# IOT_Sheet.net
KiCad netlist of a schematic drawn in Altium Designer
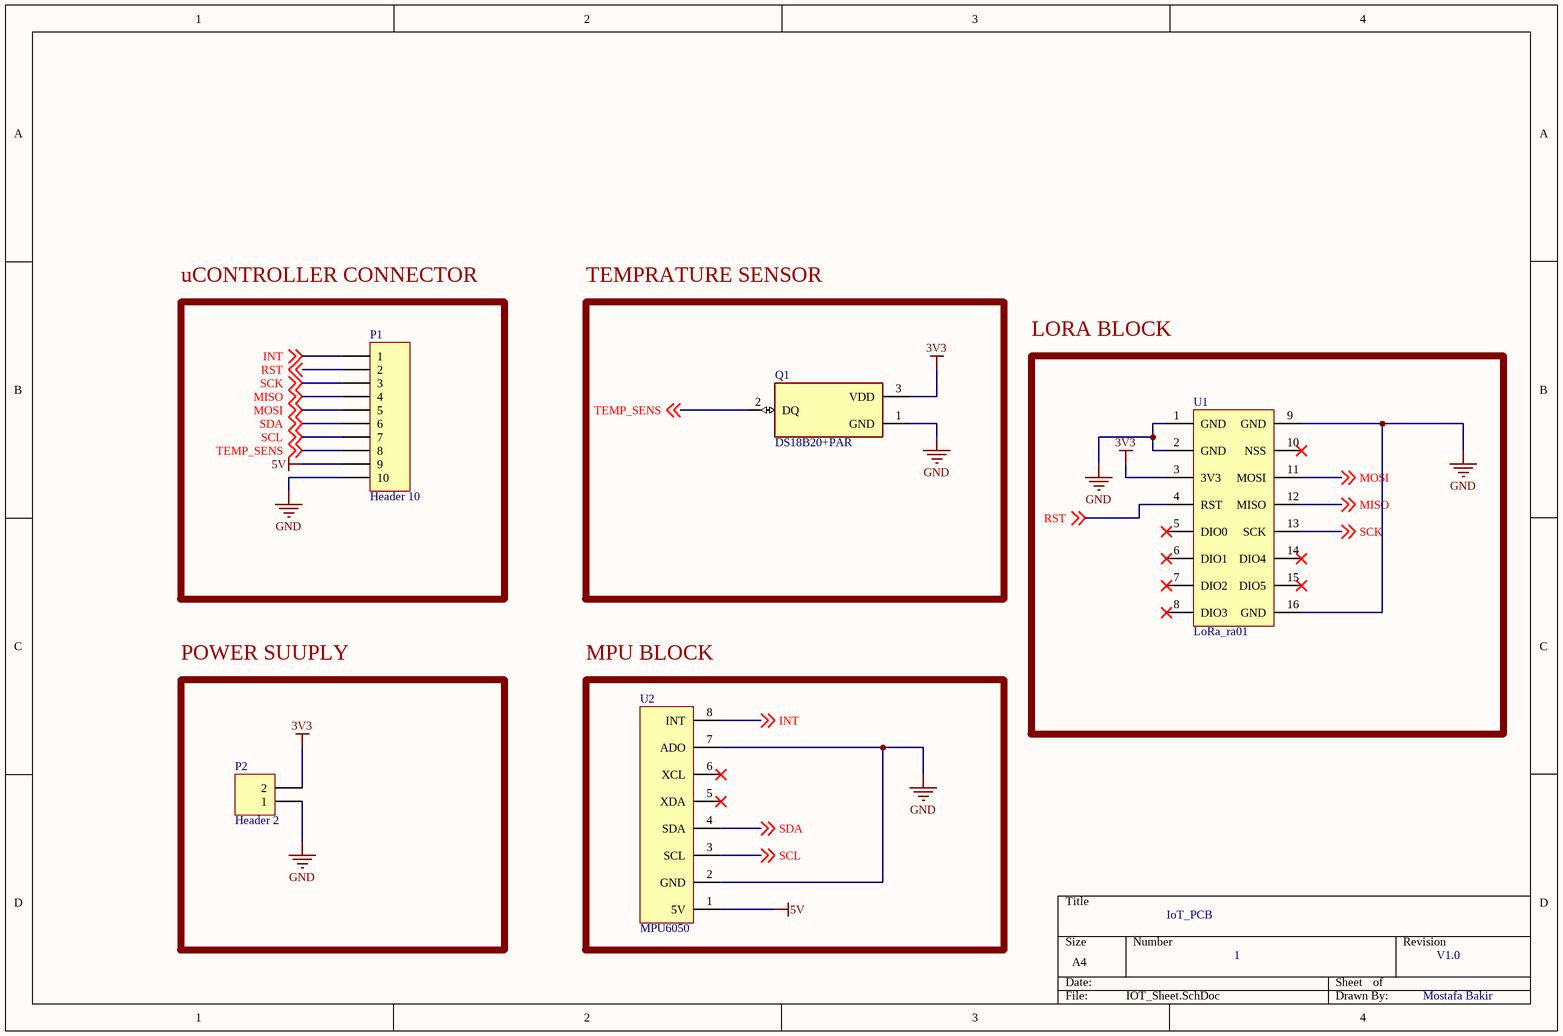
[diagram p0: IOT_Sheet.SchDoc]

(export (version "E")
  (design (tool "Eeschema 10.0.6"))
  (components
    (comp (ref "P1")
      (value "Header 10")
      (footprint "HDR1X10")
      (description "Header, 10-Pin")
      (fields (field (name "PUBLISHER") "Altium Limited"))
      (libsource (lib "Miscellaneous Connectors") (part "Header 10"))
    )
    (comp (ref "P2")
      (value "Header 2")
      (footprint "HDR1X2")
      (description "Header, 2-Pin")
      (fields (field (name "PUBLISHER") "Altium Limited"))
      (libsource (lib "Miscellaneous Connectors") (part "Header 2"))
    )
    (comp (ref "Q1")
      (value "DS18B20+PAR")
      (footprint "TO-92")
      (description "Temperature Sensor Digital, Local -55Â°C ~ 125Â°C 12 b TO-92-3")
      (fields (field (name "MF") "Maxim Integrated"))
      (libsource (lib "Schlib1") (part "DS18B20+PAR"))
    )
    (comp (ref "U1")
      (value "LoRa_ra01")
      (footprint "LoRa_pcblib")
      (libsource (lib "Schlib1") (part "Lora module sx1278"))
    )
    (comp (ref "U2") (value "MPU6050") (footprint "MPU6050") (libsource (lib "Schlib1") (part "MPU6050")))
  )
  (nets
    (net (code "1") (name "3V3") (class "Default")
      (node (ref "P2") (pin "2") (pinfunction "2_2") (pintype "passive"))
      (node (ref "Q1") (pin "3") (pinfunction "VDD_3") (pintype "power_in"))
      (node (ref "U1") (pin "3") (pinfunction "3V3_3") (pintype "passive"))
    )
    (net (code "2") (name "5V") (class "Default")
      (node (ref "P1") (pin "9") (pinfunction "9_9") (pintype "passive"))
      (node (ref "U2") (pin "1") (pinfunction "5V_1") (pintype "passive"))
    )
    (net (code "3") (name "GND") (class "Default")
      (node (ref "P1") (pin "10") (pinfunction "10_10") (pintype "passive"))
      (node (ref "P2") (pin "1") (pinfunction "1_1") (pintype "passive"))
      (node (ref "Q1") (pin "1") (pinfunction "GND_1") (pintype "power_in"))
      (node (ref "U1") (pin "1") (pinfunction "GND_1") (pintype "passive"))
      (node (ref "U1") (pin "16") (pinfunction "GND_16") (pintype "passive"))
      (node (ref "U1") (pin "2") (pinfunction "GND_2") (pintype "passive"))
      (node (ref "U1") (pin "9") (pinfunction "GND_9") (pintype "passive"))
      (node (ref "U2") (pin "2") (pinfunction "GND_2") (pintype "passive"))
      (node (ref "U2") (pin "7") (pinfunction "ADO_7") (pintype "passive"))
    )
    (net (code "4") (name "INT") (class "Default")
      (node (ref "P1") (pin "1") (pinfunction "1_1") (pintype "passive"))
      (node (ref "U2") (pin "8") (pinfunction "INT_8") (pintype "passive"))
    )
    (net (code "5") (name "MISO") (class "Default")
      (node (ref "P1") (pin "4") (pinfunction "4_4") (pintype "passive"))
      (node (ref "U1") (pin "12") (pinfunction "MISO_12") (pintype "passive"))
    )
    (net (code "6") (name "MOSI") (class "Default")
      (node (ref "P1") (pin "5") (pinfunction "5_5") (pintype "passive"))
      (node (ref "U1") (pin "11") (pinfunction "MOSI_11") (pintype "passive"))
    )
    (net (code "7") (name "RST") (class "Default")
      (node (ref "P1") (pin "2") (pinfunction "2_2") (pintype "passive"))
      (node (ref "U1") (pin "4") (pinfunction "RST_4") (pintype "passive"))
    )
    (net (code "8") (name "SCK") (class "Default")
      (node (ref "P1") (pin "3") (pinfunction "3_3") (pintype "passive"))
      (node (ref "U1") (pin "13") (pinfunction "SCK_13") (pintype "passive"))
    )
    (net (code "9") (name "SCL") (class "Default")
      (node (ref "P1") (pin "7") (pinfunction "7_7") (pintype "passive"))
      (node (ref "U2") (pin "3") (pinfunction "SCL_3") (pintype "passive"))
    )
    (net (code "10") (name "SDA") (class "Default")
      (node (ref "P1") (pin "6") (pinfunction "6_6") (pintype "passive"))
      (node (ref "U2") (pin "4") (pinfunction "SDA_4") (pintype "passive"))
    )
    (net (code "11") (name "TEMP_SENS") (class "Default")
      (node (ref "P1") (pin "8") (pinfunction "8_8") (pintype "passive"))
      (node (ref "Q1") (pin "2") (pinfunction "DQ_2") (pintype "bidirectional"))
    )
    (net (code "12") (name "unconnected-(U1-DIO0-Pad5)") (class "Default")
      (node (ref "U1") (pin "5") (pinfunction "DIO0_5") (pintype "passive+no_connect"))
    )
    (net (code "13") (name "unconnected-(U1-DIO1-Pad6)") (class "Default")
      (node (ref "U1") (pin "6") (pinfunction "DIO1_6") (pintype "passive+no_connect"))
    )
    (net (code "14") (name "unconnected-(U1-DIO2-Pad7)") (class "Default")
      (node (ref "U1") (pin "7") (pinfunction "DIO2_7") (pintype "passive+no_connect"))
    )
    (net (code "15") (name "unconnected-(U1-DIO3-Pad8)") (class "Default")
      (node (ref "U1") (pin "8") (pinfunction "DIO3_8") (pintype "passive+no_connect"))
    )
    (net (code "16") (name "unconnected-(U1-DIO4-Pad14)") (class "Default")
      (node (ref "U1") (pin "14") (pinfunction "DIO4_14") (pintype "passive+no_connect"))
    )
    (net (code "17") (name "unconnected-(U1-DIO5-Pad15)") (class "Default")
      (node (ref "U1") (pin "15") (pinfunction "DIO5_15") (pintype "passive+no_connect"))
    )
    (net (code "18") (name "unconnected-(U1-NSS-Pad10)") (class "Default")
      (node (ref "U1") (pin "10") (pinfunction "NSS_10") (pintype "passive+no_connect"))
    )
    (net (code "19") (name "unconnected-(U2-XCL-Pad6)") (class "Default")
      (node (ref "U2") (pin "6") (pinfunction "XCL_6") (pintype "passive+no_connect"))
    )
    (net (code "20") (name "unconnected-(U2-XDA-Pad5)") (class "Default")
      (node (ref "U2") (pin "5") (pinfunction "XDA_5") (pintype "passive+no_connect"))
    )
  )
)
